# GauntletV2.net
KiCad netlist of a schematic drawn in EAGLE
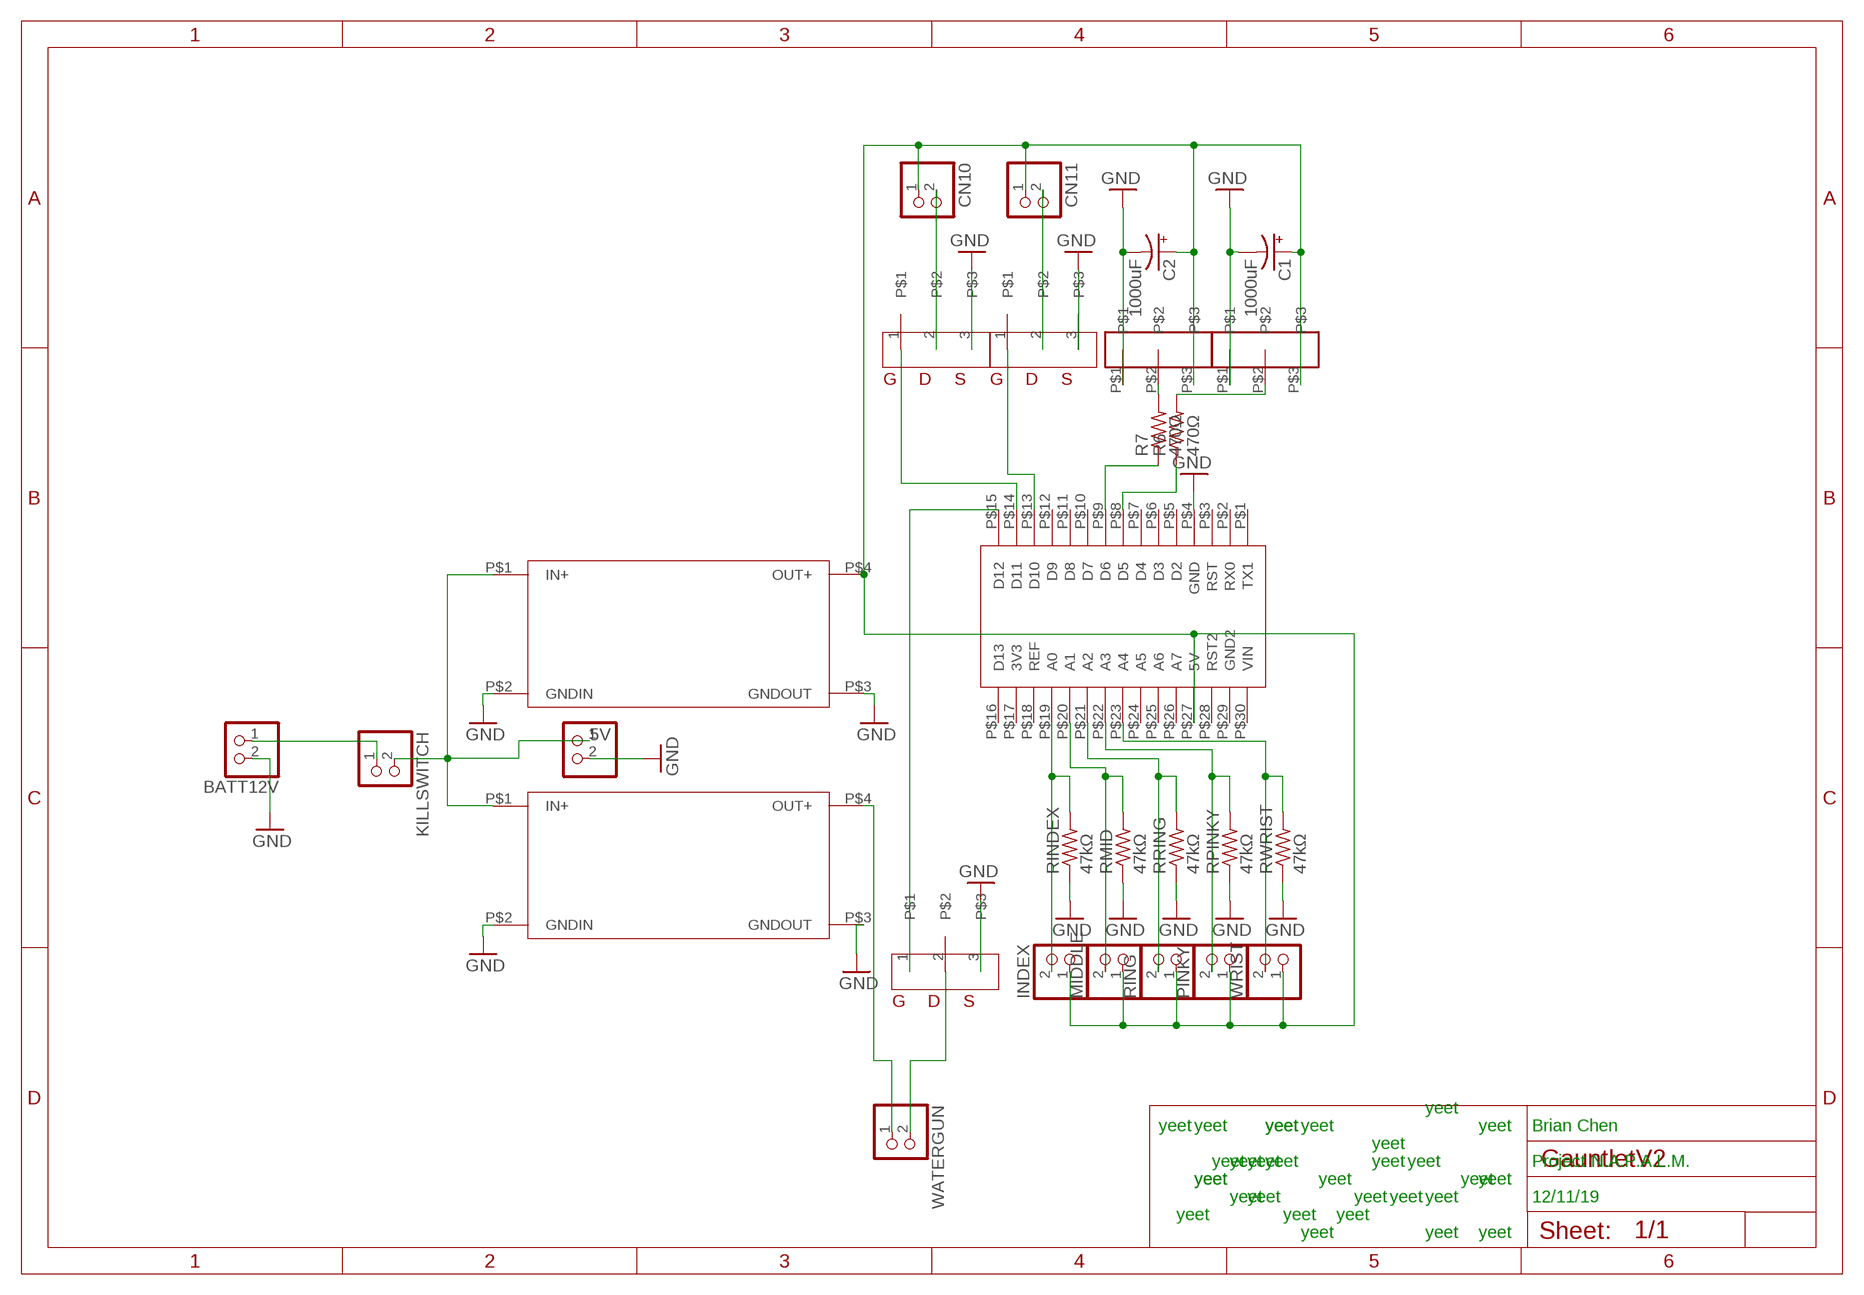
[diagram p0: schematic, sheet 1]

(export (version "E")
  (design (tool "Eeschema 10.0.6"))
  (components
    (comp (ref "5VBUCK")
      (value "LM2596BUCK")
      (footprint "eagle-import:LM2596BUCK")
      (libsource (lib "eagle-import") (part "LM2596BUCK"))
    )
    (comp (ref "6VBUCK")
      (value "LM2596BUCK")
      (footprint "eagle-import:LM2596BUCK")
      (libsource (lib "eagle-import") (part "LM2596BUCK"))
    )
    (comp (ref "BATT12V")
      (value "JST_2PIN-THM-RA")
      (footprint "eagle-import:JST-PH-2-THM-RA")
      (libsource (lib "eagle-import") (part "JST_2PIN-THM-RA"))
    )
    (comp (ref "C1")
      (value "1000uF")
      (footprint "eagle-import:E5-10,5")
      (libsource (lib "eagle-import") (part "CPOL-USE5-10.5"))
    )
    (comp (ref "C2")
      (value "1000uF")
      (footprint "eagle-import:E5-10,5")
      (libsource (lib "eagle-import") (part "CPOL-USE5-10.5"))
    )
    (comp (ref "CN10")
      (value "JST_2PIN-THM-RA")
      (footprint "eagle-import:JST-PH-2-THM-RA")
      (libsource (lib "eagle-import") (part "JST_2PIN-THM-RA"))
    )
    (comp (ref "CN11")
      (value "JST_2PIN-THM-RA")
      (footprint "eagle-import:JST-PH-2-THM-RA")
      (libsource (lib "eagle-import") (part "JST_2PIN-THM-RA"))
    )
    (comp (ref "GUNMOSFET")
      (value "TO254P1052X465X1989-3")
      (footprint "eagle-import:TO254P1052X465X1989-3")
      (libsource (lib "eagle-import") (part "TO254P1052X465X1989-3"))
    )
    (comp (ref "INDEX")
      (value "JST_2PIN-THM-RA")
      (footprint "eagle-import:JST-PH-2-THM-RA")
      (libsource (lib "eagle-import") (part "JST_2PIN-THM-RA"))
    )
    (comp (ref "KILLSWITCH")
      (value "JST_2PIN-THM-RA")
      (footprint "eagle-import:JST-PH-2-THM-RA")
      (libsource (lib "eagle-import") (part "JST_2PIN-THM-RA"))
    )
    (comp (ref "MIDDLE")
      (value "JST_2PIN-THM-RA")
      (footprint "eagle-import:JST-PH-2-THM-RA")
      (libsource (lib "eagle-import") (part "JST_2PIN-THM-RA"))
    )
    (comp (ref "NANO")
      (value "NANOV3")
      (footprint "eagle-import:NANOV3")
      (libsource (lib "eagle-import") (part "NANOV3"))
    )
    (comp (ref "PINKY")
      (value "JST_2PIN-THM-RA")
      (footprint "eagle-import:JST-PH-2-THM-RA")
      (libsource (lib "eagle-import") (part "JST_2PIN-THM-RA"))
    )
    (comp (ref "R6")
      (value "470Ω")
      (footprint "eagle-import:0207_9")
      (libsource (lib "eagle-import") (part "R-US_0207/9"))
    )
    (comp (ref "R7")
      (value "470Ω")
      (footprint "eagle-import:0207_9")
      (libsource (lib "eagle-import") (part "R-US_0207/9"))
    )
    (comp (ref "RINDEX")
      (value "47kΩ")
      (footprint "eagle-import:0207_9")
      (libsource (lib "eagle-import") (part "R-US_0207/9"))
    )
    (comp (ref "RING")
      (value "JST_2PIN-THM-RA")
      (footprint "eagle-import:JST-PH-2-THM-RA")
      (libsource (lib "eagle-import") (part "JST_2PIN-THM-RA"))
    )
    (comp (ref "RMID")
      (value "47kΩ")
      (footprint "eagle-import:0207_9")
      (libsource (lib "eagle-import") (part "R-US_0207/9"))
    )
    (comp (ref "RPINKY")
      (value "47kΩ")
      (footprint "eagle-import:0207_9")
      (libsource (lib "eagle-import") (part "R-US_0207/9"))
    )
    (comp (ref "RRING")
      (value "47kΩ")
      (footprint "eagle-import:0207_9")
      (libsource (lib "eagle-import") (part "R-US_0207/9"))
    )
    (comp (ref "RWRIST")
      (value "47kΩ")
      (footprint "eagle-import:0207_9")
      (libsource (lib "eagle-import") (part "R-US_0207/9"))
    )
    (comp (ref "U$4")
      (value "TO254P1052X465X1989-3")
      (footprint "eagle-import:TO254P1052X465X1989-3")
      (libsource (lib "eagle-import") (part "TO254P1052X465X1989-3"))
    )
    (comp (ref "U$5")
      (value "TO254P1052X465X1989-3")
      (footprint "eagle-import:TO254P1052X465X1989-3")
      (libsource (lib "eagle-import") (part "TO254P1052X465X1989-3"))
    )
    (comp (ref "U$7")
      (value "3WIRECONNECTOR")
      (footprint "eagle-import:3WIRECONNECTOR")
      (libsource (lib "eagle-import") (part "3WIRECONNECTOR"))
    )
    (comp (ref "U$8")
      (value "3WIRECONNECTOR")
      (footprint "eagle-import:3WIRECONNECTOR")
      (libsource (lib "eagle-import") (part "3WIRECONNECTOR"))
    )
    (comp (ref "VOLTMETER")
      (value "JST_2PIN-THM-RA")
      (footprint "eagle-import:JST-PH-2-THM-RA")
      (libsource (lib "eagle-import") (part "JST_2PIN-THM-RA"))
    )
    (comp (ref "WATERGUN")
      (value "JST_2PIN-THM-RA")
      (footprint "eagle-import:JST-PH-2-THM-RA")
      (libsource (lib "eagle-import") (part "JST_2PIN-THM-RA"))
    )
    (comp (ref "WRIST")
      (value "JST_2PIN-THM-RA")
      (footprint "eagle-import:JST-PH-2-THM-RA")
      (libsource (lib "eagle-import") (part "JST_2PIN-THM-RA"))
    )
  )
  (nets
    (net (code "1") (name "/5V") (class "Default")
      (node (ref "5VBUCK") (pin "P$1") (pinfunction "IN+_P$1") (pintype "bidirectional"))
      (node (ref "6VBUCK") (pin "P$1") (pinfunction "IN+_P$1") (pintype "bidirectional"))
      (node (ref "KILLSWITCH") (pin "2") (pinfunction "1_2") (pintype "passive"))
      (node (ref "VOLTMETER") (pin "1") (pinfunction "2_1") (pintype "passive"))
    )
    (net (code "2") (name "GND") (class "Default")
      (node (ref "5VBUCK") (pin "P$2") (pinfunction "GNDIN_P$2") (pintype "bidirectional"))
      (node (ref "5VBUCK") (pin "P$3") (pinfunction "GNDOUT_P$3") (pintype "bidirectional"))
      (node (ref "6VBUCK") (pin "P$2") (pinfunction "GNDIN_P$2") (pintype "bidirectional"))
      (node (ref "6VBUCK") (pin "P$3") (pinfunction "GNDOUT_P$3") (pintype "bidirectional"))
      (node (ref "BATT12V") (pin "2") (pinfunction "1_2") (pintype "passive"))
      (node (ref "C1") (pin "-") (pinfunction "-_-") (pintype "passive"))
      (node (ref "C2") (pin "-") (pinfunction "-_-") (pintype "passive"))
      (node (ref "GUNMOSFET") (pin "3") (pinfunction "P$3_3") (pintype "bidirectional"))
      (node (ref "NANO") (pin "P$4") (pinfunction "GND_P$4") (pintype "bidirectional"))
      (node (ref "RINDEX") (pin "1") (pinfunction "1_1") (pintype "passive"))
      (node (ref "RMID") (pin "1") (pinfunction "1_1") (pintype "passive"))
      (node (ref "RPINKY") (pin "1") (pinfunction "1_1") (pintype "passive"))
      (node (ref "RRING") (pin "1") (pinfunction "1_1") (pintype "passive"))
      (node (ref "RWRIST") (pin "1") (pinfunction "1_1") (pintype "passive"))
      (node (ref "U$4") (pin "3") (pinfunction "P$3_3") (pintype "bidirectional"))
      (node (ref "U$5") (pin "3") (pinfunction "P$3_3") (pintype "bidirectional"))
      (node (ref "U$7") (pin "P$1") (pinfunction "P$1_P$1") (pintype "bidirectional"))
      (node (ref "U$8") (pin "P$1") (pinfunction "P$1_P$1") (pintype "bidirectional"))
      (node (ref "VOLTMETER") (pin "2") (pinfunction "1_2") (pintype "passive"))
    )
    (net (code "3") (name "Net-(5VBUCK-OUT+)") (class "Default")
      (node (ref "5VBUCK") (pin "P$4") (pinfunction "OUT+_P$4") (pintype "bidirectional"))
      (node (ref "C1") (pin "+") (pinfunction "+_+") (pintype "passive"))
      (node (ref "C2") (pin "+") (pinfunction "+_+") (pintype "passive"))
      (node (ref "CN10") (pin "1") (pinfunction "2_1") (pintype "passive"))
      (node (ref "CN11") (pin "1") (pinfunction "2_1") (pintype "passive"))
      (node (ref "INDEX") (pin "1") (pinfunction "2_1") (pintype "passive"))
      (node (ref "MIDDLE") (pin "1") (pinfunction "2_1") (pintype "passive"))
      (node (ref "NANO") (pin "P$27") (pinfunction "5V_P$27") (pintype "bidirectional"))
      (node (ref "PINKY") (pin "1") (pinfunction "2_1") (pintype "passive"))
      (node (ref "RING") (pin "1") (pinfunction "2_1") (pintype "passive"))
      (node (ref "U$7") (pin "P$3") (pinfunction "P$3_P$3") (pintype "bidirectional"))
      (node (ref "U$8") (pin "P$3") (pinfunction "P$3_P$3") (pintype "bidirectional"))
      (node (ref "WRIST") (pin "1") (pinfunction "2_1") (pintype "passive"))
    )
    (net (code "4") (name "Net-(6VBUCK-OUT+)") (class "Default")
      (node (ref "6VBUCK") (pin "P$4") (pinfunction "OUT+_P$4") (pintype "bidirectional"))
      (node (ref "WATERGUN") (pin "1") (pinfunction "2_1") (pintype "passive"))
    )
    (net (code "5") (name "Net-(BATT12V-2)") (class "Default")
      (node (ref "BATT12V") (pin "1") (pinfunction "2_1") (pintype "passive"))
      (node (ref "KILLSWITCH") (pin "1") (pinfunction "2_1") (pintype "passive"))
    )
    (net (code "6") (name "Net-(CN10-1)") (class "Default")
      (node (ref "CN10") (pin "2") (pinfunction "1_2") (pintype "passive"))
      (node (ref "U$5") (pin "2") (pinfunction "P$2_2") (pintype "bidirectional"))
    )
    (net (code "7") (name "Net-(CN11-1)") (class "Default")
      (node (ref "CN11") (pin "2") (pinfunction "1_2") (pintype "passive"))
      (node (ref "U$4") (pin "2") (pinfunction "P$2_2") (pintype "bidirectional"))
    )
    (net (code "8") (name "Net-(GUNMOSFET-P$1)") (class "Default")
      (node (ref "GUNMOSFET") (pin "1") (pinfunction "P$1_1") (pintype "bidirectional"))
      (node (ref "NANO") (pin "P$15") (pinfunction "D12_P$15") (pintype "bidirectional"))
    )
    (net (code "9") (name "Net-(GUNMOSFET-P$2)") (class "Default")
      (node (ref "GUNMOSFET") (pin "2") (pinfunction "P$2_2") (pintype "bidirectional"))
      (node (ref "WATERGUN") (pin "2") (pinfunction "1_2") (pintype "passive"))
    )
    (net (code "10") (name "Net-(INDEX-1)") (class "Default")
      (node (ref "INDEX") (pin "2") (pinfunction "1_2") (pintype "passive"))
      (node (ref "NANO") (pin "P$19") (pinfunction "A0_P$19") (pintype "bidirectional"))
      (node (ref "RINDEX") (pin "2") (pinfunction "2_2") (pintype "passive"))
    )
    (net (code "11") (name "Net-(MIDDLE-1)") (class "Default")
      (node (ref "MIDDLE") (pin "2") (pinfunction "1_2") (pintype "passive"))
      (node (ref "NANO") (pin "P$20") (pinfunction "A1_P$20") (pintype "bidirectional"))
      (node (ref "RMID") (pin "2") (pinfunction "2_2") (pintype "passive"))
    )
    (net (code "12") (name "Net-(NANO-A2)") (class "Default")
      (node (ref "NANO") (pin "P$21") (pinfunction "A2_P$21") (pintype "bidirectional"))
      (node (ref "RING") (pin "2") (pinfunction "1_2") (pintype "passive"))
      (node (ref "RRING") (pin "2") (pinfunction "2_2") (pintype "passive"))
    )
    (net (code "13") (name "Net-(NANO-A3)") (class "Default")
      (node (ref "NANO") (pin "P$22") (pinfunction "A3_P$22") (pintype "bidirectional"))
      (node (ref "PINKY") (pin "2") (pinfunction "1_2") (pintype "passive"))
      (node (ref "RPINKY") (pin "2") (pinfunction "2_2") (pintype "passive"))
    )
    (net (code "14") (name "Net-(NANO-A4)") (class "Default")
      (node (ref "NANO") (pin "P$23") (pinfunction "A4_P$23") (pintype "bidirectional"))
      (node (ref "RWRIST") (pin "2") (pinfunction "2_2") (pintype "passive"))
      (node (ref "WRIST") (pin "2") (pinfunction "1_2") (pintype "passive"))
    )
    (net (code "15") (name "Net-(NANO-D5)") (class "Default")
      (node (ref "NANO") (pin "P$8") (pinfunction "D5_P$8") (pintype "bidirectional"))
      (node (ref "R6") (pin "1") (pinfunction "1_1") (pintype "passive"))
    )
    (net (code "16") (name "Net-(NANO-D6)") (class "Default")
      (node (ref "NANO") (pin "P$9") (pinfunction "D6_P$9") (pintype "bidirectional"))
      (node (ref "R7") (pin "1") (pinfunction "1_1") (pintype "passive"))
    )
    (net (code "17") (name "Net-(NANO-D10)") (class "Default")
      (node (ref "NANO") (pin "P$13") (pinfunction "D10_P$13") (pintype "bidirectional"))
      (node (ref "U$4") (pin "1") (pinfunction "P$1_1") (pintype "bidirectional"))
    )
    (net (code "18") (name "Net-(NANO-D11)") (class "Default")
      (node (ref "NANO") (pin "P$14") (pinfunction "D11_P$14") (pintype "bidirectional"))
      (node (ref "U$5") (pin "1") (pinfunction "P$1_1") (pintype "bidirectional"))
    )
    (net (code "19") (name "Net-(R6-Pad2)") (class "Default")
      (node (ref "R6") (pin "2") (pinfunction "2_2") (pintype "passive"))
      (node (ref "U$8") (pin "P$2") (pinfunction "P$2_P$2") (pintype "bidirectional"))
    )
    (net (code "20") (name "Net-(R7-Pad2)") (class "Default")
      (node (ref "R7") (pin "2") (pinfunction "2_2") (pintype "passive"))
      (node (ref "U$7") (pin "P$2") (pinfunction "P$2_P$2") (pintype "bidirectional"))
    )
    (net (code "21") (name "unconnected-(NANO-3V3-PadP$17)") (class "Default")
      (node (ref "NANO") (pin "P$17") (pinfunction "3V3_P$17") (pintype "bidirectional"))
    )
    (net (code "22") (name "unconnected-(NANO-A5-PadP$24)") (class "Default")
      (node (ref "NANO") (pin "P$24") (pinfunction "A5_P$24") (pintype "bidirectional"))
    )
    (net (code "23") (name "unconnected-(NANO-A6-PadP$25)") (class "Default")
      (node (ref "NANO") (pin "P$25") (pinfunction "A6_P$25") (pintype "bidirectional"))
    )
    (net (code "24") (name "unconnected-(NANO-A7-PadP$26)") (class "Default")
      (node (ref "NANO") (pin "P$26") (pinfunction "A7_P$26") (pintype "bidirectional"))
    )
    (net (code "25") (name "unconnected-(NANO-D2-PadP$5)") (class "Default")
      (node (ref "NANO") (pin "P$5") (pinfunction "D2_P$5") (pintype "bidirectional"))
    )
    (net (code "26") (name "unconnected-(NANO-D3-PadP$6)") (class "Default")
      (node (ref "NANO") (pin "P$6") (pinfunction "D3_P$6") (pintype "bidirectional"))
    )
    (net (code "27") (name "unconnected-(NANO-D4-PadP$7)") (class "Default")
      (node (ref "NANO") (pin "P$7") (pinfunction "D4_P$7") (pintype "bidirectional"))
    )
    (net (code "28") (name "unconnected-(NANO-D7-PadP$10)") (class "Default")
      (node (ref "NANO") (pin "P$10") (pinfunction "D7_P$10") (pintype "bidirectional"))
    )
    (net (code "29") (name "unconnected-(NANO-D8-PadP$11)") (class "Default")
      (node (ref "NANO") (pin "P$11") (pinfunction "D8_P$11") (pintype "bidirectional"))
    )
    (net (code "30") (name "unconnected-(NANO-D9-PadP$12)") (class "Default")
      (node (ref "NANO") (pin "P$12") (pinfunction "D9_P$12") (pintype "bidirectional"))
    )
    (net (code "31") (name "unconnected-(NANO-D13-PadP$16)") (class "Default")
      (node (ref "NANO") (pin "P$16") (pinfunction "D13_P$16") (pintype "bidirectional"))
    )
    (net (code "32") (name "unconnected-(NANO-GND2-PadP$29)") (class "Default")
      (node (ref "NANO") (pin "P$29") (pinfunction "GND2_P$29") (pintype "bidirectional"))
    )
    (net (code "33") (name "unconnected-(NANO-REF-PadP$18)") (class "Default")
      (node (ref "NANO") (pin "P$18") (pinfunction "REF_P$18") (pintype "bidirectional"))
    )
    (net (code "34") (name "unconnected-(NANO-RST-PadP$3)") (class "Default")
      (node (ref "NANO") (pin "P$3") (pinfunction "RST_P$3") (pintype "bidirectional"))
    )
    (net (code "35") (name "unconnected-(NANO-RST2-PadP$28)") (class "Default")
      (node (ref "NANO") (pin "P$28") (pinfunction "RST2_P$28") (pintype "bidirectional"))
    )
    (net (code "36") (name "unconnected-(NANO-RX0-PadP$2)") (class "Default")
      (node (ref "NANO") (pin "P$2") (pinfunction "RX0_P$2") (pintype "bidirectional"))
    )
    (net (code "37") (name "unconnected-(NANO-TX1-PadP$1)") (class "Default")
      (node (ref "NANO") (pin "P$1") (pinfunction "TX1_P$1") (pintype "bidirectional"))
    )
    (net (code "38") (name "unconnected-(NANO-VIN-PadP$30)") (class "Default")
      (node (ref "NANO") (pin "P$30") (pinfunction "VIN_P$30") (pintype "bidirectional"))
    )
  )
)
